# LPF.net
KiCad netlist of a schematic drawn in Altium Designer
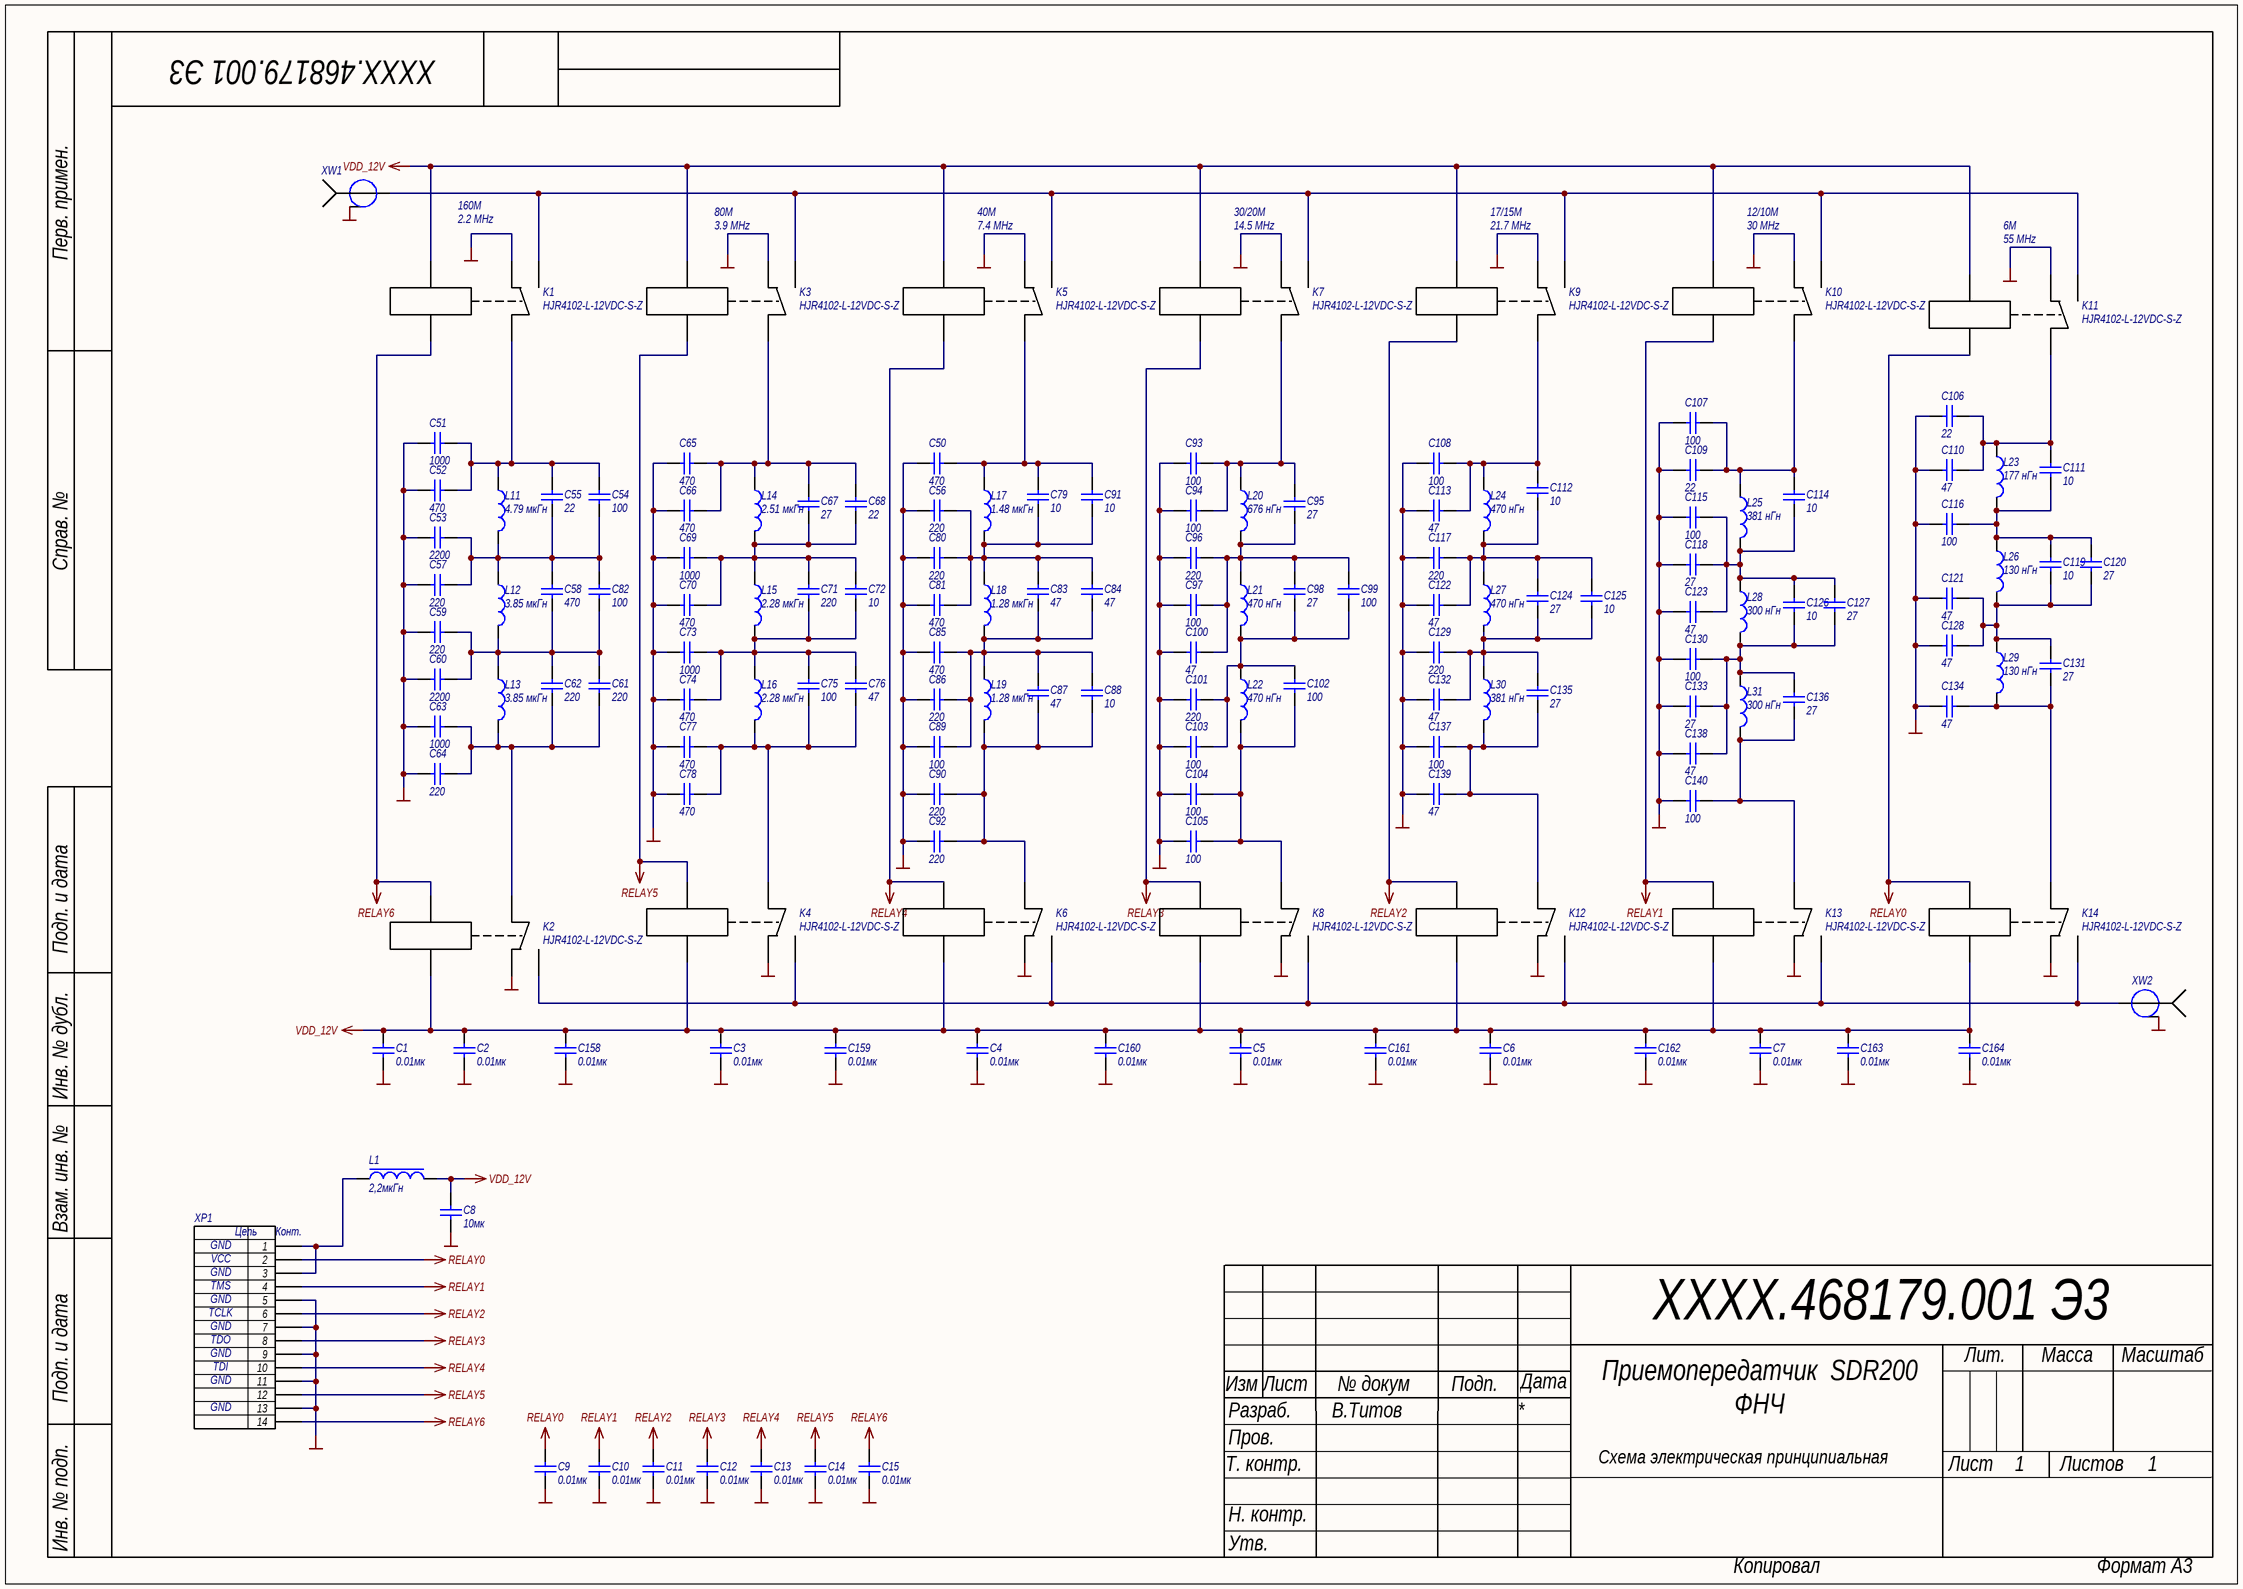
[diagram p0: LPF.SchDoc]

(export (version "E")
  (design (tool "Eeschema 10.0.6"))
  (components
    (comp (ref "C1")
      (value "0.01мк")
      (footprint "CAPC1005X06N")
      (description "Кер. ЧИП-конденсатор")
      (fields (field (name "TOLERANCE") "±20%"))
      (libsource (lib "nels_caps") (part "Кер.ЧИП конд. 0402 0.01мкФ X7R 10%, 50В"))
    )
    (comp (ref "C2")
      (value "0.01мк")
      (footprint "CAPC1005X06N")
      (description "Кер. ЧИП-конденсатор")
      (fields (field (name "TOLERANCE") "±20%"))
      (libsource (lib "nels_caps") (part "Кер.ЧИП конд. 0402 0.01мкФ X7R 10%, 50В"))
    )
    (comp (ref "C3")
      (value "0.01мк")
      (footprint "CAPC1005X06N")
      (description "Кер. ЧИП-конденсатор")
      (fields (field (name "TOLERANCE") "±20%"))
      (libsource (lib "nels_caps") (part "Кер.ЧИП конд. 0402 0.01мкФ X7R 10%, 50В"))
    )
    (comp (ref "C4")
      (value "0.01мк")
      (footprint "CAPC1005X06N")
      (description "Кер. ЧИП-конденсатор")
      (fields (field (name "TOLERANCE") "±20%"))
      (libsource (lib "nels_caps") (part "Кер.ЧИП конд. 0402 0.01мкФ X7R 10%, 50В"))
    )
    (comp (ref "C5")
      (value "0.01мк")
      (footprint "CAPC1005X06N")
      (description "Кер. ЧИП-конденсатор")
      (fields (field (name "TOLERANCE") "±20%"))
      (libsource (lib "nels_caps") (part "Кер.ЧИП конд. 0402 0.01мкФ X7R 10%, 50В"))
    )
    (comp (ref "C6")
      (value "0.01мк")
      (footprint "CAPC1005X06N")
      (description "Кер. ЧИП-конденсатор")
      (fields (field (name "TOLERANCE") "±20%"))
      (libsource (lib "nels_caps") (part "Кер.ЧИП конд. 0402 0.01мкФ X7R 10%, 50В"))
    )
    (comp (ref "C7")
      (value "0.01мк")
      (footprint "CAPC1005X06N")
      (description "Кер. ЧИП-конденсатор")
      (fields (field (name "TOLERANCE") "±20%"))
      (libsource (lib "nels_caps") (part "Кер.ЧИП конд. 0402 0.01мкФ X7R 10%, 50В"))
    )
    (comp (ref "C8")
      (value "10мк")
      (footprint "CAPC3225X27L")
      (description "Кер. ЧИП-конденсатор")
      (fields (field (name "MANUFACTURER") "Murata") (field (name "TOLERANCE") "±20%"))
      (libsource (lib "nels_caps") (part "Кер.ЧИП конд. 1210 10мкФ X5R 20% 50В"))
    )
    (comp (ref "C9")
      (value "0.01мк")
      (footprint "CAPC1005X06N")
      (description "Кер. ЧИП-конденсатор")
      (fields (field (name "TOLERANCE") "±20%"))
      (libsource (lib "nels_caps") (part "Кер.ЧИП конд. 0402 0.01мкФ X7R 10%, 50В"))
    )
    (comp (ref "C10")
      (value "0.01мк")
      (footprint "CAPC1005X06N")
      (description "Кер. ЧИП-конденсатор")
      (fields (field (name "TOLERANCE") "±20%"))
      (libsource (lib "nels_caps") (part "Кер.ЧИП конд. 0402 0.01мкФ X7R 10%, 50В"))
    )
    (comp (ref "C11")
      (value "0.01мк")
      (footprint "CAPC1005X06N")
      (description "Кер. ЧИП-конденсатор")
      (fields (field (name "TOLERANCE") "±20%"))
      (libsource (lib "nels_caps") (part "Кер.ЧИП конд. 0402 0.01мкФ X7R 10%, 50В"))
    )
    (comp (ref "C12")
      (value "0.01мк")
      (footprint "CAPC1005X06N")
      (description "Кер. ЧИП-конденсатор")
      (fields (field (name "TOLERANCE") "±20%"))
      (libsource (lib "nels_caps") (part "Кер.ЧИП конд. 0402 0.01мкФ X7R 10%, 50В"))
    )
    (comp (ref "C13")
      (value "0.01мк")
      (footprint "CAPC1005X06N")
      (description "Кер. ЧИП-конденсатор")
      (fields (field (name "TOLERANCE") "±20%"))
      (libsource (lib "nels_caps") (part "Кер.ЧИП конд. 0402 0.01мкФ X7R 10%, 50В"))
    )
    (comp (ref "C14")
      (value "0.01мк")
      (footprint "CAPC1005X06N")
      (description "Кер. ЧИП-конденсатор")
      (fields (field (name "TOLERANCE") "±20%"))
      (libsource (lib "nels_caps") (part "Кер.ЧИП конд. 0402 0.01мкФ X7R 10%, 50В"))
    )
    (comp (ref "C15")
      (value "0.01мк")
      (footprint "CAPC1005X06N")
      (description "Кер. ЧИП-конденсатор")
      (fields (field (name "TOLERANCE") "±20%"))
      (libsource (lib "nels_caps") (part "Кер.ЧИП конд. 0402 0.01мкФ X7R 10%, 50В"))
    )
    (comp (ref "C50")
      (value "470")
      (footprint "CAPC3216X19L")
      (description "Кер. ЧИП-конденсатор")
      (fields (field (name "MANUFACTURER") "WALSIN") (field (name "TOLERANCE") "±10%"))
      (libsource (lib "nels_caps") (part "Кер.ЧИП конд. 1206 470пФ NP0 10% 2000В"))
    )
    (comp (ref "C51")
      (value "1000")
      (footprint "CAPC3216X19L")
      (description "Кер. ЧИП-конденсатор")
      (fields (field (name "MANUFACTURER") "Johanson") (field (name "TOLERANCE") "±10%"))
      (libsource (lib "nels_caps") (part "Кер.ЧИП конд. 1206 1000пФ X7К 10% 2000В"))
    )
    (comp (ref "C52")
      (value "470")
      (footprint "CAPC3216X19L")
      (description "Кер. ЧИП-конденсатор")
      (fields (field (name "MANUFACTURER") "WALSIN") (field (name "TOLERANCE") "±10%"))
      (libsource (lib "nels_caps") (part "Кер.ЧИП конд. 1206 470пФ NP0 10% 2000В"))
    )
    (comp (ref "C53")
      (value "2200")
      (footprint "CAPC3216X19L")
      (description "Кер. ЧИП-конденсатор")
      (fields (field (name "MANUFACTURER") "WALSIN") (field (name "TOLERANCE") "±10%"))
      (libsource (lib "nels_caps") (part "Кер.ЧИП конд. 1206 2200пФ X7К 10% 1000В"))
    )
    (comp (ref "C54")
      (value "100")
      (footprint "CAPC3216X19L")
      (description "Кер. ЧИП-конденсатор")
      (fields (field (name "MANUFACTURER") "WALSIN") (field (name "TOLERANCE") "±5%"))
      (libsource (lib "nels_caps") (part "Кер.ЧИП конд. 1206 100пФ NP0 5% 2000В"))
    )
    (comp (ref "C55")
      (value "22")
      (footprint "CAPC3216X19L")
      (description "Кер. ЧИП-конденсатор")
      (fields (field (name "MANUFACTURER") "WALSIN") (field (name "TOLERANCE") "±5%"))
      (libsource (lib "nels_caps") (part "Кер.ЧИП конд. 1206 22пФ NP0 5% 2000В"))
    )
    (comp (ref "C56")
      (value "220")
      (footprint "CAPC3216X19L")
      (description "Кер. ЧИП-конденсатор")
      (fields (field (name "MANUFACTURER") "Johanson") (field (name "TOLERANCE") "±10%"))
      (libsource (lib "nels_caps") (part "Кер.ЧИП конд. 1206 220пФ NP0 5% 2000В"))
    )
    (comp (ref "C57")
      (value "220")
      (footprint "CAPC3216X19L")
      (description "Кер. ЧИП-конденсатор")
      (fields (field (name "MANUFACTURER") "Johanson") (field (name "TOLERANCE") "±10%"))
      (libsource (lib "nels_caps") (part "Кер.ЧИП конд. 1206 220пФ NP0 5% 2000В"))
    )
    (comp (ref "C58")
      (value "470")
      (footprint "CAPC3216X19L")
      (description "Кер. ЧИП-конденсатор")
      (fields (field (name "MANUFACTURER") "WALSIN") (field (name "TOLERANCE") "±10%"))
      (libsource (lib "nels_caps") (part "Кер.ЧИП конд. 1206 470пФ NP0 10% 2000В"))
    )
    (comp (ref "C59")
      (value "220")
      (footprint "CAPC3216X19L")
      (description "Кер. ЧИП-конденсатор")
      (fields (field (name "MANUFACTURER") "Johanson") (field (name "TOLERANCE") "±10%"))
      (libsource (lib "nels_caps") (part "Кер.ЧИП конд. 1206 220пФ NP0 5% 2000В"))
    )
    (comp (ref "C60")
      (value "2200")
      (footprint "CAPC3216X19L")
      (description "Кер. ЧИП-конденсатор")
      (fields (field (name "MANUFACTURER") "WALSIN") (field (name "TOLERANCE") "±10%"))
      (libsource (lib "nels_caps") (part "Кер.ЧИП конд. 1206 2200пФ X7К 10% 1000В"))
    )
    (comp (ref "C61")
      (value "220")
      (footprint "CAPC3216X19L")
      (description "Кер. ЧИП-конденсатор")
      (fields (field (name "MANUFACTURER") "Johanson") (field (name "TOLERANCE") "±10%"))
      (libsource (lib "nels_caps") (part "Кер.ЧИП конд. 1206 220пФ NP0 5% 2000В"))
    )
    (comp (ref "C62")
      (value "220")
      (footprint "CAPC3216X19L")
      (description "Кер. ЧИП-конденсатор")
      (fields (field (name "MANUFACTURER") "Johanson") (field (name "TOLERANCE") "±10%"))
      (libsource (lib "nels_caps") (part "Кер.ЧИП конд. 1206 220пФ NP0 5% 2000В"))
    )
    (comp (ref "C63")
      (value "1000")
      (footprint "CAPC3216X19L")
      (description "Кер. ЧИП-конденсатор")
      (fields (field (name "MANUFACTURER") "Johanson") (field (name "TOLERANCE") "±10%"))
      (libsource (lib "nels_caps") (part "Кер.ЧИП конд. 1206 1000пФ X7К 10% 2000В"))
    )
    (comp (ref "C64")
      (value "220")
      (footprint "CAPC3216X19L")
      (description "Кер. ЧИП-конденсатор")
      (fields (field (name "MANUFACTURER") "Johanson") (field (name "TOLERANCE") "±10%"))
      (libsource (lib "nels_caps") (part "Кер.ЧИП конд. 1206 220пФ NP0 5% 2000В"))
    )
    (comp (ref "C65")
      (value "470")
      (footprint "CAPC3216X19L")
      (description "Кер. ЧИП-конденсатор")
      (fields (field (name "MANUFACTURER") "WALSIN") (field (name "TOLERANCE") "±10%"))
      (libsource (lib "nels_caps") (part "Кер.ЧИП конд. 1206 470пФ NP0 10% 2000В"))
    )
    (comp (ref "C66")
      (value "470")
      (footprint "CAPC3216X19L")
      (description "Кер. ЧИП-конденсатор")
      (fields (field (name "MANUFACTURER") "WALSIN") (field (name "TOLERANCE") "±10%"))
      (libsource (lib "nels_caps") (part "Кер.ЧИП конд. 1206 470пФ NP0 10% 2000В"))
    )
    (comp (ref "C67")
      (value "27")
      (footprint "CAPC3216X19L")
      (description "Кер. ЧИП-конденсатор")
      (fields (field (name "MANUFACTURER") "WALSIN") (field (name "TOLERANCE") "±10%"))
      (libsource (lib "nels_caps") (part "Кер.ЧИП конд. 1206 27пФ NP0 10% 2000В"))
    )
    (comp (ref "C68")
      (value "22")
      (footprint "CAPC3216X19L")
      (description "Кер. ЧИП-конденсатор")
      (fields (field (name "MANUFACTURER") "WALSIN") (field (name "TOLERANCE") "±5%"))
      (libsource (lib "nels_caps") (part "Кер.ЧИП конд. 1206 22пФ NP0 5% 2000В"))
    )
    (comp (ref "C69")
      (value "1000")
      (footprint "CAPC3216X19L")
      (description "Кер. ЧИП-конденсатор")
      (fields (field (name "MANUFACTURER") "Johanson") (field (name "TOLERANCE") "±10%"))
      (libsource (lib "nels_caps") (part "Кер.ЧИП конд. 1206 1000пФ X7К 10% 2000В"))
    )
    (comp (ref "C70")
      (value "470")
      (footprint "CAPC3216X19L")
      (description "Кер. ЧИП-конденсатор")
      (fields (field (name "MANUFACTURER") "WALSIN") (field (name "TOLERANCE") "±10%"))
      (libsource (lib "nels_caps") (part "Кер.ЧИП конд. 1206 470пФ NP0 10% 2000В"))
    )
    (comp (ref "C71")
      (value "220")
      (footprint "CAPC3216X19L")
      (description "Кер. ЧИП-конденсатор")
      (fields (field (name "MANUFACTURER") "Johanson") (field (name "TOLERANCE") "±10%"))
      (libsource (lib "nels_caps") (part "Кер.ЧИП конд. 1206 220пФ NP0 5% 2000В"))
    )
    (comp (ref "C72")
      (value "10")
      (footprint "CAPC3216X19L")
      (description "Кер. ЧИП-конденсатор")
      (fields (field (name "MANUFACTURER") "WALSIN") (field (name "TOLERANCE") "±5%"))
      (libsource (lib "nels_caps") (part "Кер.ЧИП конд. 1206 10пФ NP0 5% 2000В"))
    )
    (comp (ref "C73")
      (value "1000")
      (footprint "CAPC3216X19L")
      (description "Кер. ЧИП-конденсатор")
      (fields (field (name "MANUFACTURER") "Johanson") (field (name "TOLERANCE") "±10%"))
      (libsource (lib "nels_caps") (part "Кер.ЧИП конд. 1206 1000пФ X7К 10% 2000В"))
    )
    (comp (ref "C74")
      (value "470")
      (footprint "CAPC3216X19L")
      (description "Кер. ЧИП-конденсатор")
      (fields (field (name "MANUFACTURER") "WALSIN") (field (name "TOLERANCE") "±10%"))
      (libsource (lib "nels_caps") (part "Кер.ЧИП конд. 1206 470пФ NP0 10% 2000В"))
    )
    (comp (ref "C75")
      (value "100")
      (footprint "CAPC3216X19L")
      (description "Кер. ЧИП-конденсатор")
      (fields (field (name "MANUFACTURER") "WALSIN") (field (name "TOLERANCE") "±5%"))
      (libsource (lib "nels_caps") (part "Кер.ЧИП конд. 1206 100пФ NP0 5% 2000В"))
    )
    (comp (ref "C76")
      (value "47")
      (footprint "CAPC3216X19L")
      (description "Кер. ЧИП-конденсатор")
      (fields (field (name "MANUFACTURER") "WALSIN") (field (name "TOLERANCE") "±5%"))
      (libsource (lib "nels_caps") (part "Кер.ЧИП конд. 1206 47пФ NP0 5% 2000В"))
    )
    (comp (ref "C77")
      (value "470")
      (footprint "CAPC3216X19L")
      (description "Кер. ЧИП-конденсатор")
      (fields (field (name "MANUFACTURER") "WALSIN") (field (name "TOLERANCE") "±10%"))
      (libsource (lib "nels_caps") (part "Кер.ЧИП конд. 1206 470пФ NP0 10% 2000В"))
    )
    (comp (ref "C78")
      (value "470")
      (footprint "CAPC3216X19L")
      (description "Кер. ЧИП-конденсатор")
      (fields (field (name "MANUFACTURER") "WALSIN") (field (name "TOLERANCE") "±10%"))
      (libsource (lib "nels_caps") (part "Кер.ЧИП конд. 1206 470пФ NP0 10% 2000В"))
    )
    (comp (ref "C79")
      (value "10")
      (footprint "CAPC3216X19L")
      (description "Кер. ЧИП-конденсатор")
      (fields (field (name "MANUFACTURER") "WALSIN") (field (name "TOLERANCE") "±5%"))
      (libsource (lib "nels_caps") (part "Кер.ЧИП конд. 1206 10пФ NP0 5% 2000В"))
    )
    (comp (ref "C80")
      (value "220")
      (footprint "CAPC3216X19L")
      (description "Кер. ЧИП-конденсатор")
      (fields (field (name "MANUFACTURER") "Johanson") (field (name "TOLERANCE") "±10%"))
      (libsource (lib "nels_caps") (part "Кер.ЧИП конд. 1206 220пФ NP0 5% 2000В"))
    )
    (comp (ref "C81")
      (value "470")
      (footprint "CAPC3216X19L")
      (description "Кер. ЧИП-конденсатор")
      (fields (field (name "MANUFACTURER") "WALSIN") (field (name "TOLERANCE") "±10%"))
      (libsource (lib "nels_caps") (part "Кер.ЧИП конд. 1206 470пФ NP0 10% 2000В"))
    )
    (comp (ref "C82")
      (value "100")
      (footprint "CAPC3216X19L")
      (description "Кер. ЧИП-конденсатор")
      (fields (field (name "MANUFACTURER") "WALSIN") (field (name "TOLERANCE") "±5%"))
      (libsource (lib "nels_caps") (part "Кер.ЧИП конд. 1206 100пФ NP0 5% 2000В"))
    )
    (comp (ref "C83")
      (value "47")
      (footprint "CAPC3216X19L")
      (description "Кер. ЧИП-конденсатор")
      (fields (field (name "MANUFACTURER") "WALSIN") (field (name "TOLERANCE") "±5%"))
      (libsource (lib "nels_caps") (part "Кер.ЧИП конд. 1206 47пФ NP0 5% 2000В"))
    )
    (comp (ref "C84")
      (value "47")
      (footprint "CAPC3216X19L")
      (description "Кер. ЧИП-конденсатор")
      (fields (field (name "MANUFACTURER") "WALSIN") (field (name "TOLERANCE") "±5%"))
      (libsource (lib "nels_caps") (part "Кер.ЧИП конд. 1206 47пФ NP0 5% 2000В"))
    )
    (comp (ref "C85")
      (value "470")
      (footprint "CAPC3216X19L")
      (description "Кер. ЧИП-конденсатор")
      (fields (field (name "MANUFACTURER") "WALSIN") (field (name "TOLERANCE") "±10%"))
      (libsource (lib "nels_caps") (part "Кер.ЧИП конд. 1206 470пФ NP0 10% 2000В"))
    )
    (comp (ref "C86")
      (value "220")
      (footprint "CAPC3216X19L")
      (description "Кер. ЧИП-конденсатор")
      (fields (field (name "MANUFACTURER") "Johanson") (field (name "TOLERANCE") "±10%"))
      (libsource (lib "nels_caps") (part "Кер.ЧИП конд. 1206 220пФ NP0 5% 2000В"))
    )
    (comp (ref "C87")
      (value "47")
      (footprint "CAPC3216X19L")
      (description "Кер. ЧИП-конденсатор")
      (fields (field (name "MANUFACTURER") "WALSIN") (field (name "TOLERANCE") "±5%"))
      (libsource (lib "nels_caps") (part "Кер.ЧИП конд. 1206 47пФ NP0 5% 2000В"))
    )
    (comp (ref "C88")
      (value "10")
      (footprint "CAPC3216X19L")
      (description "Кер. ЧИП-конденсатор")
      (fields (field (name "MANUFACTURER") "WALSIN") (field (name "TOLERANCE") "±5%"))
      (libsource (lib "nels_caps") (part "Кер.ЧИП конд. 1206 10пФ NP0 5% 2000В"))
    )
    (comp (ref "C89")
      (value "100")
      (footprint "CAPC3216X19L")
      (description "Кер. ЧИП-конденсатор")
      (fields (field (name "MANUFACTURER") "WALSIN") (field (name "TOLERANCE") "±5%"))
      (libsource (lib "nels_caps") (part "Кер.ЧИП конд. 1206 100пФ NP0 5% 2000В"))
    )
    (comp (ref "C90")
      (value "220")
      (footprint "CAPC3216X19L")
      (description "Кер. ЧИП-конденсатор")
      (fields (field (name "MANUFACTURER") "Johanson") (field (name "TOLERANCE") "±10%"))
      (libsource (lib "nels_caps") (part "Кер.ЧИП конд. 1206 220пФ NP0 5% 2000В"))
    )
    (comp (ref "C91")
      (value "10")
      (footprint "CAPC3216X19L")
      (description "Кер. ЧИП-конденсатор")
      (fields (field (name "MANUFACTURER") "WALSIN") (field (name "TOLERANCE") "±5%"))
      (libsource (lib "nels_caps") (part "Кер.ЧИП конд. 1206 10пФ NP0 5% 2000В"))
    )
    (comp (ref "C92")
      (value "220")
      (footprint "CAPC3216X19L")
      (description "Кер. ЧИП-конденсатор")
      (fields (field (name "MANUFACTURER") "Johanson") (field (name "TOLERANCE") "±10%"))
      (libsource (lib "nels_caps") (part "Кер.ЧИП конд. 1206 220пФ NP0 5% 2000В"))
    )
    (comp (ref "C93")
      (value "100")
      (footprint "CAPC3216X19L")
      (description "Кер. ЧИП-конденсатор")
      (fields (field (name "MANUFACTURER") "WALSIN") (field (name "TOLERANCE") "±5%"))
      (libsource (lib "nels_caps") (part "Кер.ЧИП конд. 1206 100пФ NP0 5% 2000В"))
    )
    (comp (ref "C94")
      (value "100")
      (footprint "CAPC3216X19L")
      (description "Кер. ЧИП-конденсатор")
      (fields (field (name "MANUFACTURER") "WALSIN") (field (name "TOLERANCE") "±5%"))
      (libsource (lib "nels_caps") (part "Кер.ЧИП конд. 1206 100пФ NP0 5% 2000В"))
    )
    (comp (ref "C95")
      (value "27")
      (footprint "CAPC3216X19L")
      (description "Кер. ЧИП-конденсатор")
      (fields (field (name "MANUFACTURER") "WALSIN") (field (name "TOLERANCE") "±10%"))
      (libsource (lib "nels_caps") (part "Кер.ЧИП конд. 1206 27пФ NP0 10% 2000В"))
    )
    (comp (ref "C96")
      (value "220")
      (footprint "CAPC3216X19L")
      (description "Кер. ЧИП-конденсатор")
      (fields (field (name "MANUFACTURER") "Johanson") (field (name "TOLERANCE") "±10%"))
      (libsource (lib "nels_caps") (part "Кер.ЧИП конд. 1206 220пФ NP0 5% 2000В"))
    )
    (comp (ref "C97")
      (value "100")
      (footprint "CAPC3216X19L")
      (description "Кер. ЧИП-конденсатор")
      (fields (field (name "MANUFACTURER") "WALSIN") (field (name "TOLERANCE") "±5%"))
      (libsource (lib "nels_caps") (part "Кер.ЧИП конд. 1206 100пФ NP0 5% 2000В"))
    )
    (comp (ref "C98")
      (value "27")
      (footprint "CAPC3216X19L")
      (description "Кер. ЧИП-конденсатор")
      (fields (field (name "MANUFACTURER") "WALSIN") (field (name "TOLERANCE") "±10%"))
      (libsource (lib "nels_caps") (part "Кер.ЧИП конд. 1206 27пФ NP0 10% 2000В"))
    )
    (comp (ref "C99")
      (value "100")
      (footprint "CAPC3216X19L")
      (description "Кер. ЧИП-конденсатор")
      (fields (field (name "MANUFACTURER") "WALSIN") (field (name "TOLERANCE") "±5%"))
      (libsource (lib "nels_caps") (part "Кер.ЧИП конд. 1206 100пФ NP0 5% 2000В"))
    )
    (comp (ref "C100")
      (value "47")
      (footprint "CAPC3216X19L")
      (description "Кер. ЧИП-конденсатор")
      (fields (field (name "MANUFACTURER") "WALSIN") (field (name "TOLERANCE") "±5%"))
      (libsource (lib "nels_caps") (part "Кер.ЧИП конд. 1206 47пФ NP0 5% 2000В"))
    )
    (comp (ref "C101")
      (value "220")
      (footprint "CAPC3216X19L")
      (description "Кер. ЧИП-конденсатор")
      (fields (field (name "MANUFACTURER") "Johanson") (field (name "TOLERANCE") "±10%"))
      (libsource (lib "nels_caps") (part "Кер.ЧИП конд. 1206 220пФ NP0 5% 2000В"))
    )
    (comp (ref "C102")
      (value "100")
      (footprint "CAPC3216X19L")
      (description "Кер. ЧИП-конденсатор")
      (fields (field (name "MANUFACTURER") "WALSIN") (field (name "TOLERANCE") "±5%"))
      (libsource (lib "nels_caps") (part "Кер.ЧИП конд. 1206 100пФ NP0 5% 2000В"))
    )
    (comp (ref "C103")
      (value "100")
      (footprint "CAPC3216X19L")
      (description "Кер. ЧИП-конденсатор")
      (fields (field (name "MANUFACTURER") "WALSIN") (field (name "TOLERANCE") "±5%"))
      (libsource (lib "nels_caps") (part "Кер.ЧИП конд. 1206 100пФ NP0 5% 2000В"))
    )
    (comp (ref "C104")
      (value "100")
      (footprint "CAPC3216X19L")
      (description "Кер. ЧИП-конденсатор")
      (fields (field (name "MANUFACTURER") "WALSIN") (field (name "TOLERANCE") "±5%"))
      (libsource (lib "nels_caps") (part "Кер.ЧИП конд. 1206 100пФ NP0 5% 2000В"))
    )
    (comp (ref "C105")
      (value "100")
      (footprint "CAPC3216X19L")
      (description "Кер. ЧИП-конденсатор")
      (fields (field (name "MANUFACTURER") "WALSIN") (field (name "TOLERANCE") "±5%"))
      (libsource (lib "nels_caps") (part "Кер.ЧИП конд. 1206 100пФ NP0 5% 2000В"))
    )
    (comp (ref "C106")
      (value "22")
      (footprint "CAPC3216X19L")
      (description "Кер. ЧИП-конденсатор")
      (fields (field (name "MANUFACTURER") "WALSIN") (field (name "TOLERANCE") "±5%"))
      (libsource (lib "nels_caps") (part "Кер.ЧИП конд. 1206 22пФ NP0 5% 2000В"))
    )
    (comp (ref "C107")
      (value "100")
      (footprint "CAPC3216X19L")
      (description "Кер. ЧИП-конденсатор")
      (fields (field (name "MANUFACTURER") "WALSIN") (field (name "TOLERANCE") "±5%"))
      (libsource (lib "nels_caps") (part "Кер.ЧИП конд. 1206 100пФ NP0 5% 2000В"))
    )
    (comp (ref "C108")
      (value "100")
      (footprint "CAPC3216X19L")
      (description "Кер. ЧИП-конденсатор")
      (fields (field (name "MANUFACTURER") "WALSIN") (field (name "TOLERANCE") "±5%"))
      (libsource (lib "nels_caps") (part "Кер.ЧИП конд. 1206 100пФ NP0 5% 2000В"))
    )
    (comp (ref "C109")
      (value "22")
      (footprint "CAPC3216X19L")
      (description "Кер. ЧИП-конденсатор")
      (fields (field (name "MANUFACTURER") "WALSIN") (field (name "TOLERANCE") "±5%"))
      (libsource (lib "nels_caps") (part "Кер.ЧИП конд. 1206 22пФ NP0 5% 2000В"))
    )
    (comp (ref "C110")
      (value "47")
      (footprint "CAPC3216X19L")
      (description "Кер. ЧИП-конденсатор")
      (fields (field (name "MANUFACTURER") "WALSIN") (field (name "TOLERANCE") "±5%"))
      (libsource (lib "nels_caps") (part "Кер.ЧИП конд. 1206 47пФ NP0 5% 2000В"))
    )
    (comp (ref "C111")
      (value "10")
      (footprint "CAPC3216X19L")
      (description "Кер. ЧИП-конденсатор")
      (fields (field (name "MANUFACTURER") "WALSIN") (field (name "TOLERANCE") "±5%"))
      (libsource (lib "nels_caps") (part "Кер.ЧИП конд. 1206 10пФ NP0 5% 2000В"))
    )
    (comp (ref "C112")
      (value "10")
      (footprint "CAPC3216X19L")
      (description "Кер. ЧИП-конденсатор")
      (fields (field (name "MANUFACTURER") "WALSIN") (field (name "TOLERANCE") "±5%"))
      (libsource (lib "nels_caps") (part "Кер.ЧИП конд. 1206 10пФ NP0 5% 2000В"))
    )
    (comp (ref "C113")
      (value "47")
      (footprint "CAPC3216X19L")
      (description "Кер. ЧИП-конденсатор")
      (fields (field (name "MANUFACTURER") "WALSIN") (field (name "TOLERANCE") "±5%"))
      (libsource (lib "nels_caps") (part "Кер.ЧИП конд. 1206 47пФ NP0 5% 2000В"))
    )
    (comp (ref "C114")
      (value "10")
      (footprint "CAPC3216X19L")
      (description "Кер. ЧИП-конденсатор")
      (fields (field (name "MANUFACTURER") "WALSIN") (field (name "TOLERANCE") "±5%"))
      (libsource (lib "nels_caps") (part "Кер.ЧИП конд. 1206 10пФ NP0 5% 2000В"))
    )
    (comp (ref "C115")
      (value "100")
      (footprint "CAPC3216X19L")
      (description "Кер. ЧИП-конденсатор")
      (fields (field (name "MANUFACTURER") "WALSIN") (field (name "TOLERANCE") "±5%"))
      (libsource (lib "nels_caps") (part "Кер.ЧИП конд. 1206 100пФ NP0 5% 2000В"))
    )
    (comp (ref "C116")
      (value "100")
      (footprint "CAPC3216X19L")
      (description "Кер. ЧИП-конденсатор")
      (fields (field (name "MANUFACTURER") "WALSIN") (field (name "TOLERANCE") "±5%"))
      (libsource (lib "nels_caps") (part "Кер.ЧИП конд. 1206 100пФ NP0 5% 2000В"))
    )
    (comp (ref "C117")
      (value "220")
      (footprint "CAPC3216X19L")
      (description "Кер. ЧИП-конденсатор")
      (fields (field (name "MANUFACTURER") "Johanson") (field (name "TOLERANCE") "±10%"))
      (libsource (lib "nels_caps") (part "Кер.ЧИП конд. 1206 220пФ NP0 5% 2000В"))
    )
    (comp (ref "C118")
      (value "27")
      (footprint "CAPC3216X19L")
      (description "Кер. ЧИП-конденсатор")
      (fields (field (name "MANUFACTURER") "WALSIN") (field (name "TOLERANCE") "±10%"))
      (libsource (lib "nels_caps") (part "Кер.ЧИП конд. 1206 27пФ NP0 10% 2000В"))
    )
    (comp (ref "C119")
      (value "10")
      (footprint "CAPC3216X19L")
      (description "Кер. ЧИП-конденсатор")
      (fields (field (name "MANUFACTURER") "WALSIN") (field (name "TOLERANCE") "±5%"))
      (libsource (lib "nels_caps") (part "Кер.ЧИП конд. 1206 10пФ NP0 5% 2000В"))
    )
    (comp (ref "C120")
      (value "27")
      (footprint "CAPC3216X19L")
      (description "Кер. ЧИП-конденсатор")
      (fields (field (name "MANUFACTURER") "WALSIN") (field (name "TOLERANCE") "±10%"))
      (libsource (lib "nels_caps") (part "Кер.ЧИП конд. 1206 27пФ NP0 10% 2000В"))
    )
    (comp (ref "C121")
      (value "47")
      (footprint "CAPC3216X19L")
      (description "Кер. ЧИП-конденсатор")
      (fields (field (name "MANUFACTURER") "WALSIN") (field (name "TOLERANCE") "±5%"))
      (libsource (lib "nels_caps") (part "Кер.ЧИП конд. 1206 47пФ NP0 5% 2000В"))
    )
    (comp (ref "C122")
      (value "47")
      (footprint "CAPC3216X19L")
      (description "Кер. ЧИП-конденсатор")
      (fields (field (name "MANUFACTURER") "WALSIN") (field (name "TOLERANCE") "±5%"))
      (libsource (lib "nels_caps") (part "Кер.ЧИП конд. 1206 47пФ NP0 5% 2000В"))
    )
    (comp (ref "C123")
      (value "47")
      (footprint "CAPC3216X19L")
      (description "Кер. ЧИП-конденсатор")
      (fields (field (name "MANUFACTURER") "WALSIN") (field (name "TOLERANCE") "±5%"))
      (libsource (lib "nels_caps") (part "Кер.ЧИП конд. 1206 47пФ NP0 5% 2000В"))
    )
    (comp (ref "C124")
      (value "27")
      (footprint "CAPC3216X19L")
      (description "Кер. ЧИП-конденсатор")
      (fields (field (name "MANUFACTURER") "WALSIN") (field (name "TOLERANCE") "±10%"))
      (libsource (lib "nels_caps") (part "Кер.ЧИП конд. 1206 27пФ NP0 10% 2000В"))
    )
    (comp (ref "C125")
      (value "10")
      (footprint "CAPC3216X19L")
      (description "Кер. ЧИП-конденсатор")
      (fields (field (name "MANUFACTURER") "WALSIN") (field (name "TOLERANCE") "±5%"))
      (libsource (lib "nels_caps") (part "Кер.ЧИП конд. 1206 10пФ NP0 5% 2000В"))
    )
    (comp (ref "C126")
      (value "10")
      (footprint "CAPC3216X19L")
      (description "Кер. ЧИП-конденсатор")
      (fields (field (name "MANUFACTURER") "WALSIN") (field (name "TOLERANCE") "±5%"))
      (libsource (lib "nels_caps") (part "Кер.ЧИП конд. 1206 10пФ NP0 5% 2000В"))
    )
    (comp (ref "C127")
      (value "27")
      (footprint "CAPC3216X19L")
      (description "Кер. ЧИП-конденсатор")
      (fields (field (name "MANUFACTURER") "WALSIN") (field (name "TOLERANCE") "±10%"))
      (libsource (lib "nels_caps") (part "Кер.ЧИП конд. 1206 27пФ NP0 10% 2000В"))
    )
    (comp (ref "C128")
      (value "47")
      (footprint "CAPC3216X19L")
      (description "Кер. ЧИП-конденсатор")
      (fields (field (name "MANUFACTURER") "WALSIN") (field (name "TOLERANCE") "±5%"))
      (libsource (lib "nels_caps") (part "Кер.ЧИП конд. 1206 47пФ NP0 5% 2000В"))
    )
    (comp (ref "C129")
      (value "220")
      (footprint "CAPC3216X19L")
      (description "Кер. ЧИП-конденсатор")
      (fields (field (name "MANUFACTURER") "Johanson") (field (name "TOLERANCE") "±10%"))
      (libsource (lib "nels_caps") (part "Кер.ЧИП конд. 1206 220пФ NP0 5% 2000В"))
    )
    (comp (ref "C130")
      (value "100")
      (footprint "CAPC3216X19L")
      (description "Кер. ЧИП-конденсатор")
      (fields (field (name "MANUFACTURER") "WALSIN") (field (name "TOLERANCE") "±5%"))
      (libsource (lib "nels_caps") (part "Кер.ЧИП конд. 1206 100пФ NP0 5% 2000В"))
    )
    (comp (ref "C131")
      (value "27")
      (footprint "CAPC3216X19L")
      (description "Кер. ЧИП-конденсатор")
      (fields (field (name "MANUFACTURER") "WALSIN") (field (name "TOLERANCE") "±10%"))
      (libsource (lib "nels_caps") (part "Кер.ЧИП конд. 1206 27пФ NP0 10% 2000В"))
    )
    (comp (ref "C132")
      (value "47")
      (footprint "CAPC3216X19L")
      (description "Кер. ЧИП-конденсатор")
      (fields (field (name "MANUFACTURER") "WALSIN") (field (name "TOLERANCE") "±5%"))
      (libsource (lib "nels_caps") (part "Кер.ЧИП конд. 1206 47пФ NP0 5% 2000В"))
    )
    (comp (ref "C133")
      (value "27")
      (footprint "CAPC3216X19L")
      (description "Кер. ЧИП-конденсатор")
      (fields (field (name "MANUFACTURER") "WALSIN") (field (name "TOLERANCE") "±10%"))
      (libsource (lib "nels_caps") (part "Кер.ЧИП конд. 1206 27пФ NP0 10% 2000В"))
    )
    (comp (ref "C134")
      (value "47")
      (footprint "CAPC3216X19L")
      (description "Кер. ЧИП-конденсатор")
      (fields (field (name "MANUFACTURER") "WALSIN") (field (name "TOLERANCE") "±5%"))
      (libsource (lib "nels_caps") (part "Кер.ЧИП конд. 1206 47пФ NP0 5% 2000В"))
    )
    (comp (ref "C135")
      (value "27")
      (footprint "CAPC3216X19L")
      (description "Кер. ЧИП-конденсатор")
      (fields (field (name "MANUFACTURER") "WALSIN") (field (name "TOLERANCE") "±10%"))
      (libsource (lib "nels_caps") (part "Кер.ЧИП конд. 1206 27пФ NP0 10% 2000В"))
    )
    (comp (ref "C136")
      (value "27")
      (footprint "CAPC3216X19L")
      (description "Кер. ЧИП-конденсатор")
      (fields (field (name "MANUFACTURER") "WALSIN") (field (name "TOLERANCE") "±10%"))
      (libsource (lib "nels_caps") (part "Кер.ЧИП конд. 1206 27пФ NP0 10% 2000В"))
    )
    (comp (ref "C137")
      (value "100")
      (footprint "CAPC3216X19L")
      (description "Кер. ЧИП-конденсатор")
      (fields (field (name "MANUFACTURER") "WALSIN") (field (name "TOLERANCE") "±5%"))
      (libsource (lib "nels_caps") (part "Кер.ЧИП конд. 1206 100пФ NP0 5% 2000В"))
    )
    (comp (ref "C138")
      (value "47")
      (footprint "CAPC3216X19L")
      (description "Кер. ЧИП-конденсатор")
      (fields (field (name "MANUFACTURER") "WALSIN") (field (name "TOLERANCE") "±5%"))
      (libsource (lib "nels_caps") (part "Кер.ЧИП конд. 1206 47пФ NP0 5% 2000В"))
    )
    (comp (ref "C139")
      (value "47")
      (footprint "CAPC3216X19L")
      (description "Кер. ЧИП-конденсатор")
      (fields (field (name "MANUFACTURER") "WALSIN") (field (name "TOLERANCE") "±5%"))
      (libsource (lib "nels_caps") (part "Кер.ЧИП конд. 1206 47пФ NP0 5% 2000В"))
    )
    (comp (ref "C140")
      (value "100")
      (footprint "CAPC3216X19L")
      (description "Кер. ЧИП-конденсатор")
      (fields (field (name "MANUFACTURER") "WALSIN") (field (name "TOLERANCE") "±5%"))
      (libsource (lib "nels_caps") (part "Кер.ЧИП конд. 1206 100пФ NP0 5% 2000В"))
    )
    (comp (ref "C158")
      (value "0.01мк")
      (footprint "CAPC1005X06N")
      (description "Кер. ЧИП-конденсатор")
      (fields (field (name "TOLERANCE") "±20%"))
      (libsource (lib "nels_caps") (part "Кер.ЧИП конд. 0402 0.01мкФ X7R 10%, 50В"))
    )
    (comp (ref "C159")
      (value "0.01мк")
      (footprint "CAPC1005X06N")
      (description "Кер. ЧИП-конденсатор")
      (fields (field (name "TOLERANCE") "±20%"))
      (libsource (lib "nels_caps") (part "Кер.ЧИП конд. 0402 0.01мкФ X7R 10%, 50В"))
    )
    (comp (ref "C160")
      (value "0.01мк")
      (footprint "CAPC1005X06N")
      (description "Кер. ЧИП-конденсатор")
      (fields (field (name "TOLERANCE") "±20%"))
      (libsource (lib "nels_caps") (part "Кер.ЧИП конд. 0402 0.01мкФ X7R 10%, 50В"))
    )
    (comp (ref "C161")
      (value "0.01мк")
      (footprint "CAPC1005X06N")
      (description "Кер. ЧИП-конденсатор")
      (fields (field (name "TOLERANCE") "±20%"))
      (libsource (lib "nels_caps") (part "Кер.ЧИП конд. 0402 0.01мкФ X7R 10%, 50В"))
    )
    (comp (ref "C162")
      (value "0.01мк")
      (footprint "CAPC1005X06N")
      (description "Кер. ЧИП-конденсатор")
      (fields (field (name "TOLERANCE") "±20%"))
      (libsource (lib "nels_caps") (part "Кер.ЧИП конд. 0402 0.01мкФ X7R 10%, 50В"))
    )
    (comp (ref "C163")
      (value "0.01мк")
      (footprint "CAPC1005X06N")
      (description "Кер. ЧИП-конденсатор")
      (fields (field (name "TOLERANCE") "±20%"))
      (libsource (lib "nels_caps") (part "Кер.ЧИП конд. 0402 0.01мкФ X7R 10%, 50В"))
    )
    (comp (ref "C164")
      (value "0.01мк")
      (footprint "CAPC1005X06N")
      (description "Кер. ЧИП-конденсатор")
      (fields (field (name "TOLERANCE") "±20%"))
      (libsource (lib "nels_caps") (part "Кер.ЧИП конд. 0402 0.01мкФ X7R 10%, 50В"))
    )
    (comp (ref "K1")
      (value "HJR4102-L-12VDC-S-Z")
      (footprint "HJR4102")
      (description "Реле 1пер. 12VDC, 1A/240VAC")
      (libsource (lib "nels_other") (part "Реле HJR4102-L-12VDC-S-Z"))
    )
    (comp (ref "K2")
      (value "HJR4102-L-12VDC-S-Z")
      (footprint "HJR4102")
      (description "Реле 1пер. 12VDC, 1A/240VAC")
      (libsource (lib "nels_other") (part "Реле HJR4102-L-12VDC-S-Z"))
    )
    (comp (ref "K3")
      (value "HJR4102-L-12VDC-S-Z")
      (footprint "HJR4102")
      (description "Реле 1пер. 12VDC, 1A/240VAC")
      (libsource (lib "nels_other") (part "Реле HJR4102-L-12VDC-S-Z"))
    )
    (comp (ref "K4")
      (value "HJR4102-L-12VDC-S-Z")
      (footprint "HJR4102")
      (description "Реле 1пер. 12VDC, 1A/240VAC")
      (libsource (lib "nels_other") (part "Реле HJR4102-L-12VDC-S-Z"))
    )
    (comp (ref "K5")
      (value "HJR4102-L-12VDC-S-Z")
      (footprint "HJR4102")
      (description "Реле 1пер. 12VDC, 1A/240VAC")
      (libsource (lib "nels_other") (part "Реле HJR4102-L-12VDC-S-Z"))
    )
    (comp (ref "K6")
      (value "HJR4102-L-12VDC-S-Z")
      (footprint "HJR4102")
      (description "Реле 1пер. 12VDC, 1A/240VAC")
      (libsource (lib "nels_other") (part "Реле HJR4102-L-12VDC-S-Z"))
    )
    (comp (ref "K7")
      (value "HJR4102-L-12VDC-S-Z")
      (footprint "HJR4102")
      (description "Реле 1пер. 12VDC, 1A/240VAC")
      (libsource (lib "nels_other") (part "Реле HJR4102-L-12VDC-S-Z"))
    )
    (comp (ref "K8")
      (value "HJR4102-L-12VDC-S-Z")
      (footprint "HJR4102")
      (description "Реле 1пер. 12VDC, 1A/240VAC")
      (libsource (lib "nels_other") (part "Реле HJR4102-L-12VDC-S-Z"))
    )
    (comp (ref "K9")
      (value "HJR4102-L-12VDC-S-Z")
      (footprint "HJR4102")
      (description "Реле 1пер. 12VDC, 1A/240VAC")
      (libsource (lib "nels_other") (part "Реле HJR4102-L-12VDC-S-Z"))
    )
    (comp (ref "K10")
      (value "HJR4102-L-12VDC-S-Z")
      (footprint "HJR4102")
      (description "Реле 1пер. 12VDC, 1A/240VAC")
      (libsource (lib "nels_other") (part "Реле HJR4102-L-12VDC-S-Z"))
    )
    (comp (ref "K11")
      (value "HJR4102-L-12VDC-S-Z")
      (footprint "HJR4102")
      (description "Реле 1пер. 12VDC, 1A/240VAC")
      (libsource (lib "nels_other") (part "Реле HJR4102-L-12VDC-S-Z"))
    )
    (comp (ref "K12")
      (value "HJR4102-L-12VDC-S-Z")
      (footprint "HJR4102")
      (description "Реле 1пер. 12VDC, 1A/240VAC")
      (libsource (lib "nels_other") (part "Реле HJR4102-L-12VDC-S-Z"))
    )
    (comp (ref "K13")
      (value "HJR4102-L-12VDC-S-Z")
      (footprint "HJR4102")
      (description "Реле 1пер. 12VDC, 1A/240VAC")
      (libsource (lib "nels_other") (part "Реле HJR4102-L-12VDC-S-Z"))
    )
    (comp (ref "K14")
      (value "HJR4102-L-12VDC-S-Z")
      (footprint "HJR4102")
      (description "Реле 1пер. 12VDC, 1A/240VAC")
      (libsource (lib "nels_other") (part "Реле HJR4102-L-12VDC-S-Z"))
    )
    (comp (ref "L1")
      (value "2,2мкГн")
      (footprint "CSAB0420")
      (description "Molding Power Choke")
      (fields
        (field (name "MANUFACTURER") "Vishay")
        (field (name "MANUFACTURERPARTNUMBER") "IHLP1616ABER1R0M11")
      )
      (libsource (lib "nels_ind") (part "ЧИП индуктивность CSAB0420-2R2M"))
    )
    (comp (ref "L11")
      (value "4.79 мкГн")
      (footprint "T68-2")
      (description "29 витков")
      (libsource (lib "nels_ind") (part "Индуктивность T68-2 4.79 мкГн"))
    )
    (comp (ref "L12")
      (value "3.85 мкГн")
      (footprint "T68-2")
      (description "26 витков")
      (libsource (lib "nels_ind") (part "Индуктивность T68-2 3.85 мкГн"))
    )
    (comp (ref "L13")
      (value "3.85 мкГн")
      (footprint "T68-2")
      (description "26 витков")
      (libsource (lib "nels_ind") (part "Индуктивность T68-2 3.85 мкГн"))
    )
    (comp (ref "L14")
      (value "2.51 мкГн")
      (footprint "T68-2")
      (description "21 виток")
      (libsource (lib "nels_ind") (part "Индуктивность T68-2 2.51 мкГн"))
    )
    (comp (ref "L15")
      (value "2.28 мкГн")
      (footprint "T68-2")
      (libsource (lib "nels_ind") (part "Индуктивность T68-2 2.28 мкГн"))
    )
    (comp (ref "L16")
      (value "2.28 мкГн")
      (footprint "T68-2")
      (libsource (lib "nels_ind") (part "Индуктивность T68-2 2.28 мкГн"))
    )
    (comp (ref "L17")
      (value "1.48 мкГн")
      (footprint "T68-2")
      (description "16 витков")
      (libsource (lib "nels_ind") (part "Индуктивность T68-2 1.48 мкГн"))
    )
    (comp (ref "L18")
      (value "1.28 мкГн")
      (footprint "T68-2")
      (description "16 витков")
      (libsource (lib "nels_ind") (part "Индуктивность T68-2 1.28 мкГн"))
    )
    (comp (ref "L19")
      (value "1.28 мкГн")
      (footprint "T68-2")
      (description "16 витков")
      (libsource (lib "nels_ind") (part "Индуктивность T68-2 1.28 мкГн"))
    )
    (comp (ref "L20")
      (value "676 нГн")
      (footprint "T68-6")
      (description "12 витков")
      (libsource (lib "nels_ind") (part "Индуктивность T68-6 676 нГн"))
    )
    (comp (ref "L21")
      (value "470 нГн")
      (footprint "T68-6")
      (description "10 витков")
      (libsource (lib "nels_ind") (part "Индуктивность T68-6 470 нГн"))
    )
    (comp (ref "L22")
      (value "470 нГн")
      (footprint "T68-6")
      (description "10 витков")
      (libsource (lib "nels_ind") (part "Индуктивность T68-6 470 нГн"))
    )
    (comp (ref "L23")
      (value "177 нГн")
      (footprint "COIL D11 W4 L6")
      (description "4 витка, диаметр 11мм, длина 6мм")
      (libsource (lib "nels_ind") (part "Индуктивность 177 нГн"))
    )
    (comp (ref "L24")
      (value "470 нГн")
      (footprint "T68-6")
      (description "10 витков")
      (libsource (lib "nels_ind") (part "Индуктивность T68-6 470 нГн"))
    )
    (comp (ref "L25")
      (value "381 нГн")
      (footprint "T68-6")
      (description "9 витков")
      (libsource (lib "nels_ind") (part "Индуктивность T68-6 381 нГн"))
    )
    (comp (ref "L26")
      (value "130 нГн")
      (footprint "COIL D11 W4 L10")
      (description "4 витка, диаметр 11мм, длина 10мм")
      (libsource (lib "nels_ind") (part "Индуктивность 130 нГн"))
    )
    (comp (ref "L27")
      (value "470 нГн")
      (footprint "T68-6")
      (description "10 витков")
      (libsource (lib "nels_ind") (part "Индуктивность T68-6 470 нГн"))
    )
    (comp (ref "L28")
      (value "300 нГн")
      (footprint "T68-6")
      (description "8 витков")
      (libsource (lib "nels_ind") (part "Индуктивность T68-6 300 нГн"))
    )
    (comp (ref "L29")
      (value "130 нГн")
      (footprint "COIL D11 W4 L10")
      (description "4 витка, диаметр 11мм, длина 10мм")
      (libsource (lib "nels_ind") (part "Индуктивность 130 нГн"))
    )
    (comp (ref "L30")
      (value "381 нГн")
      (footprint "T68-6")
      (description "9 витков")
      (libsource (lib "nels_ind") (part "Индуктивность T68-6 381 нГн"))
    )
    (comp (ref "L31")
      (value "300 нГн")
      (footprint "T68-6")
      (description "8 витков")
      (libsource (lib "nels_ind") (part "Индуктивность T68-6 300 нГн"))
    )
    (comp (ref "XP1")
      (value "IDC2-14MS")
      (footprint "IDC2-14MS")
      (description "JTAG Xilinx IDC2-14MS")
      (fields (field (name "MANUFACTURER") "Molex"))
      (libsource (lib "nels_conn") (part "Соединитель IDC2-14MS"))
    )
    (comp (ref "XW1")
      (value "SMA-JR")
      (footprint "SMA-JR")
      (description "SMA-JR Разъем SMA гнездо на плату, прямой угол")
      (libsource (lib "") (part "Соединитель коаксиальный SMA-JR_1"))
    )
    (comp (ref "XW2")
      (value "SMA-JR")
      (footprint "SMA-JR")
      (description "SMA-JR Разъем SMA гнездо на плату, прямой угол")
      (libsource (lib "nels_conn") (part "Соединитель коаксиальный SMA-JR"))
    )
  )
  (nets
    (net (code "1") (name "GND") (class "Default")
      (node (ref "C1") (pin "1") (pinfunction "1_1") (pintype "passive"))
      (node (ref "C10") (pin "1") (pinfunction "1_1") (pintype "passive"))
      (node (ref "C100") (pin "2") (pinfunction "2_2") (pintype "passive"))
      (node (ref "C101") (pin "2") (pinfunction "2_2") (pintype "passive"))
      (node (ref "C103") (pin "2") (pinfunction "2_2") (pintype "passive"))
      (node (ref "C104") (pin "2") (pinfunction "2_2") (pintype "passive"))
      (node (ref "C105") (pin "2") (pinfunction "2_2") (pintype "passive"))
      (node (ref "C106") (pin "2") (pinfunction "2_2") (pintype "passive"))
      (node (ref "C107") (pin "2") (pinfunction "2_2") (pintype "passive"))
      (node (ref "C108") (pin "2") (pinfunction "2_2") (pintype "passive"))
      (node (ref "C109") (pin "2") (pinfunction "2_2") (pintype "passive"))
      (node (ref "C11") (pin "1") (pinfunction "1_1") (pintype "passive"))
      (node (ref "C110") (pin "2") (pinfunction "2_2") (pintype "passive"))
      (node (ref "C113") (pin "2") (pinfunction "2_2") (pintype "passive"))
      (node (ref "C115") (pin "2") (pinfunction "2_2") (pintype "passive"))
      (node (ref "C116") (pin "2") (pinfunction "2_2") (pintype "passive"))
      (node (ref "C117") (pin "2") (pinfunction "2_2") (pintype "passive"))
      (node (ref "C118") (pin "2") (pinfunction "2_2") (pintype "passive"))
      (node (ref "C12") (pin "1") (pinfunction "1_1") (pintype "passive"))
      (node (ref "C121") (pin "2") (pinfunction "2_2") (pintype "passive"))
      (node (ref "C122") (pin "2") (pinfunction "2_2") (pintype "passive"))
      (node (ref "C123") (pin "2") (pinfunction "2_2") (pintype "passive"))
      (node (ref "C128") (pin "2") (pinfunction "2_2") (pintype "passive"))
      (node (ref "C129") (pin "2") (pinfunction "2_2") (pintype "passive"))
      (node (ref "C13") (pin "1") (pinfunction "1_1") (pintype "passive"))
      (node (ref "C130") (pin "2") (pinfunction "2_2") (pintype "passive"))
      (node (ref "C132") (pin "2") (pinfunction "2_2") (pintype "passive"))
      (node (ref "C133") (pin "2") (pinfunction "2_2") (pintype "passive"))
      (node (ref "C134") (pin "2") (pinfunction "2_2") (pintype "passive"))
      (node (ref "C137") (pin "2") (pinfunction "2_2") (pintype "passive"))
      (node (ref "C138") (pin "2") (pinfunction "2_2") (pintype "passive"))
      (node (ref "C139") (pin "2") (pinfunction "2_2") (pintype "passive"))
      (node (ref "C14") (pin "1") (pinfunction "1_1") (pintype "passive"))
      (node (ref "C140") (pin "2") (pinfunction "2_2") (pintype "passive"))
      (node (ref "C15") (pin "1") (pinfunction "1_1") (pintype "passive"))
      (node (ref "C158") (pin "1") (pinfunction "1_1") (pintype "passive"))
      (node (ref "C159") (pin "1") (pinfunction "1_1") (pintype "passive"))
      (node (ref "C160") (pin "1") (pinfunction "1_1") (pintype "passive"))
      (node (ref "C161") (pin "1") (pinfunction "1_1") (pintype "passive"))
      (node (ref "C162") (pin "1") (pinfunction "1_1") (pintype "passive"))
      (node (ref "C163") (pin "1") (pinfunction "1_1") (pintype "passive"))
      (node (ref "C164") (pin "1") (pinfunction "1_1") (pintype "passive"))
      (node (ref "C2") (pin "1") (pinfunction "1_1") (pintype "passive"))
      (node (ref "C3") (pin "1") (pinfunction "1_1") (pintype "passive"))
      (node (ref "C4") (pin "1") (pinfunction "1_1") (pintype "passive"))
      (node (ref "C5") (pin "1") (pinfunction "1_1") (pintype "passive"))
      (node (ref "C50") (pin "2") (pinfunction "2_2") (pintype "passive"))
      (node (ref "C51") (pin "2") (pinfunction "2_2") (pintype "passive"))
      (node (ref "C52") (pin "2") (pinfunction "2_2") (pintype "passive"))
      (node (ref "C53") (pin "2") (pinfunction "2_2") (pintype "passive"))
      (node (ref "C56") (pin "2") (pinfunction "2_2") (pintype "passive"))
      (node (ref "C57") (pin "2") (pinfunction "2_2") (pintype "passive"))
      (node (ref "C59") (pin "2") (pinfunction "2_2") (pintype "passive"))
      (node (ref "C6") (pin "1") (pinfunction "1_1") (pintype "passive"))
      (node (ref "C60") (pin "2") (pinfunction "2_2") (pintype "passive"))
      (node (ref "C63") (pin "2") (pinfunction "2_2") (pintype "passive"))
      (node (ref "C64") (pin "2") (pinfunction "2_2") (pintype "passive"))
      (node (ref "C65") (pin "2") (pinfunction "2_2") (pintype "passive"))
      (node (ref "C66") (pin "2") (pinfunction "2_2") (pintype "passive"))
      (node (ref "C69") (pin "2") (pinfunction "2_2") (pintype "passive"))
      (node (ref "C7") (pin "1") (pinfunction "1_1") (pintype "passive"))
      (node (ref "C70") (pin "2") (pinfunction "2_2") (pintype "passive"))
      (node (ref "C73") (pin "2") (pinfunction "2_2") (pintype "passive"))
      (node (ref "C74") (pin "2") (pinfunction "2_2") (pintype "passive"))
      (node (ref "C77") (pin "2") (pinfunction "2_2") (pintype "passive"))
      (node (ref "C78") (pin "2") (pinfunction "2_2") (pintype "passive"))
      (node (ref "C8") (pin "1") (pinfunction "1_1") (pintype "passive"))
      (node (ref "C80") (pin "2") (pinfunction "2_2") (pintype "passive"))
      (node (ref "C81") (pin "2") (pinfunction "2_2") (pintype "passive"))
      (node (ref "C85") (pin "2") (pinfunction "2_2") (pintype "passive"))
      (node (ref "C86") (pin "2") (pinfunction "2_2") (pintype "passive"))
      (node (ref "C89") (pin "2") (pinfunction "2_2") (pintype "passive"))
      (node (ref "C9") (pin "1") (pinfunction "1_1") (pintype "passive"))
      (node (ref "C90") (pin "2") (pinfunction "2_2") (pintype "passive"))
      (node (ref "C92") (pin "2") (pinfunction "2_2") (pintype "passive"))
      (node (ref "C93") (pin "2") (pinfunction "2_2") (pintype "passive"))
      (node (ref "C94") (pin "2") (pinfunction "2_2") (pintype "passive"))
      (node (ref "C96") (pin "2") (pinfunction "2_2") (pintype "passive"))
      (node (ref "C97") (pin "2") (pinfunction "2_2") (pintype "passive"))
      (node (ref "K1") (pin "7") (pintype "passive"))
      (node (ref "K10") (pin "7") (pintype "passive"))
      (node (ref "K11") (pin "7") (pintype "passive"))
      (node (ref "K12") (pin "7") (pintype "passive"))
      (node (ref "K13") (pin "7") (pintype "passive"))
      (node (ref "K14") (pin "7") (pintype "passive"))
      (node (ref "K2") (pin "7") (pintype "passive"))
      (node (ref "K3") (pin "7") (pintype "passive"))
      (node (ref "K4") (pin "7") (pintype "passive"))
      (node (ref "K5") (pin "7") (pintype "passive"))
      (node (ref "K6") (pin "7") (pintype "passive"))
      (node (ref "K7") (pin "7") (pintype "passive"))
      (node (ref "K8") (pin "7") (pintype "passive"))
      (node (ref "K9") (pin "7") (pintype "passive"))
      (node (ref "XP1") (pin "11") (pinfunction "11_11") (pintype "passive"))
      (node (ref "XP1") (pin "13") (pinfunction "13_13") (pintype "passive"))
      (node (ref "XP1") (pin "5") (pinfunction "5_5") (pintype "passive"))
      (node (ref "XP1") (pin "7") (pinfunction "7_7") (pintype "passive"))
      (node (ref "XP1") (pin "9") (pinfunction "9_9") (pintype "passive"))
      (node (ref "XW1") (pin "2") (pinfunction "2_2") (pintype "passive"))
      (node (ref "XW2") (pin "2") (pinfunction "2_2") (pintype "passive"))
    )
    (net (code "2") (name "Net-(C50-Pad1)") (class "Default")
      (node (ref "C50") (pin "1") (pinfunction "1_1") (pintype "passive"))
      (node (ref "C79") (pin "2") (pinfunction "2_2") (pintype "passive"))
      (node (ref "C91") (pin "2") (pinfunction "2_2") (pintype "passive"))
      (node (ref "K5") (pin "12") (pintype "passive"))
      (node (ref "L17") (pin "1") (pinfunction "1_1") (pintype "passive"))
    )
    (net (code "3") (name "Net-(C51-Pad1)") (class "Default")
      (node (ref "C51") (pin "1") (pinfunction "1_1") (pintype "passive"))
      (node (ref "C52") (pin "1") (pinfunction "1_1") (pintype "passive"))
      (node (ref "C54") (pin "2") (pinfunction "2_2") (pintype "passive"))
      (node (ref "C55") (pin "2") (pinfunction "2_2") (pintype "passive"))
      (node (ref "K1") (pin "12") (pintype "passive"))
      (node (ref "L11") (pin "1") (pinfunction "1_1") (pintype "passive"))
    )
    (net (code "4") (name "Net-(C53-Pad1)") (class "Default")
      (node (ref "C53") (pin "1") (pinfunction "1_1") (pintype "passive"))
      (node (ref "C54") (pin "1") (pinfunction "1_1") (pintype "passive"))
      (node (ref "C55") (pin "1") (pinfunction "1_1") (pintype "passive"))
      (node (ref "C57") (pin "1") (pinfunction "1_1") (pintype "passive"))
      (node (ref "C58") (pin "2") (pinfunction "2_2") (pintype "passive"))
      (node (ref "C82") (pin "2") (pinfunction "2_2") (pintype "passive"))
      (node (ref "L11") (pin "2") (pinfunction "2_2") (pintype "passive"))
      (node (ref "L12") (pin "1") (pinfunction "1_1") (pintype "passive"))
    )
    (net (code "5") (name "Net-(C56-Pad1)") (class "Default")
      (node (ref "C56") (pin "1") (pinfunction "1_1") (pintype "passive"))
      (node (ref "C79") (pin "1") (pinfunction "1_1") (pintype "passive"))
      (node (ref "C80") (pin "1") (pinfunction "1_1") (pintype "passive"))
      (node (ref "C81") (pin "1") (pinfunction "1_1") (pintype "passive"))
      (node (ref "C83") (pin "2") (pinfunction "2_2") (pintype "passive"))
      (node (ref "C84") (pin "2") (pinfunction "2_2") (pintype "passive"))
      (node (ref "C91") (pin "1") (pinfunction "1_1") (pintype "passive"))
      (node (ref "L17") (pin "2") (pinfunction "2_2") (pintype "passive"))
      (node (ref "L18") (pin "1") (pinfunction "1_1") (pintype "passive"))
    )
    (net (code "6") (name "Net-(C58-Pad1)") (class "Default")
      (node (ref "C58") (pin "1") (pinfunction "1_1") (pintype "passive"))
      (node (ref "C59") (pin "1") (pinfunction "1_1") (pintype "passive"))
      (node (ref "C60") (pin "1") (pinfunction "1_1") (pintype "passive"))
      (node (ref "C61") (pin "2") (pinfunction "2_2") (pintype "passive"))
      (node (ref "C62") (pin "2") (pinfunction "2_2") (pintype "passive"))
      (node (ref "C82") (pin "1") (pinfunction "1_1") (pintype "passive"))
      (node (ref "L12") (pin "2") (pinfunction "2_2") (pintype "passive"))
      (node (ref "L13") (pin "1") (pinfunction "1_1") (pintype "passive"))
    )
    (net (code "7") (name "Net-(C61-Pad1)") (class "Default")
      (node (ref "C61") (pin "1") (pinfunction "1_1") (pintype "passive"))
      (node (ref "C62") (pin "1") (pinfunction "1_1") (pintype "passive"))
      (node (ref "C63") (pin "1") (pinfunction "1_1") (pintype "passive"))
      (node (ref "C64") (pin "1") (pinfunction "1_1") (pintype "passive"))
      (node (ref "K2") (pin "12") (pintype "passive"))
      (node (ref "L13") (pin "2") (pinfunction "2_2") (pintype "passive"))
    )
    (net (code "8") (name "Net-(C65-Pad1)") (class "Default")
      (node (ref "C65") (pin "1") (pinfunction "1_1") (pintype "passive"))
      (node (ref "C66") (pin "1") (pinfunction "1_1") (pintype "passive"))
      (node (ref "C67") (pin "2") (pinfunction "2_2") (pintype "passive"))
      (node (ref "C68") (pin "2") (pinfunction "2_2") (pintype "passive"))
      (node (ref "K3") (pin "12") (pintype "passive"))
      (node (ref "L14") (pin "1") (pinfunction "1_1") (pintype "passive"))
    )
    (net (code "9") (name "Net-(C67-Pad1)") (class "Default")
      (node (ref "C67") (pin "1") (pinfunction "1_1") (pintype "passive"))
      (node (ref "C68") (pin "1") (pinfunction "1_1") (pintype "passive"))
      (node (ref "C69") (pin "1") (pinfunction "1_1") (pintype "passive"))
      (node (ref "C70") (pin "1") (pinfunction "1_1") (pintype "passive"))
      (node (ref "C71") (pin "1") (pinfunction "1_1") (pintype "passive"))
      (node (ref "C72") (pin "2") (pinfunction "2_2") (pintype "passive"))
      (node (ref "L14") (pin "2") (pinfunction "2_2") (pintype "passive"))
      (node (ref "L15") (pin "1") (pinfunction "1_1") (pintype "passive"))
    )
    (net (code "10") (name "Net-(C71-Pad2)") (class "Default")
      (node (ref "C71") (pin "2") (pinfunction "2_2") (pintype "passive"))
      (node (ref "C72") (pin "1") (pinfunction "1_1") (pintype "passive"))
      (node (ref "C73") (pin "1") (pinfunction "1_1") (pintype "passive"))
      (node (ref "C74") (pin "1") (pinfunction "1_1") (pintype "passive"))
      (node (ref "C75") (pin "2") (pinfunction "2_2") (pintype "passive"))
      (node (ref "C76") (pin "2") (pinfunction "2_2") (pintype "passive"))
      (node (ref "L15") (pin "2") (pinfunction "2_2") (pintype "passive"))
      (node (ref "L16") (pin "1") (pinfunction "1_1") (pintype "passive"))
    )
    (net (code "11") (name "Net-(C75-Pad1)") (class "Default")
      (node (ref "C75") (pin "1") (pinfunction "1_1") (pintype "passive"))
      (node (ref "C76") (pin "1") (pinfunction "1_1") (pintype "passive"))
      (node (ref "C77") (pin "1") (pinfunction "1_1") (pintype "passive"))
      (node (ref "C78") (pin "1") (pinfunction "1_1") (pintype "passive"))
      (node (ref "K4") (pin "12") (pintype "passive"))
      (node (ref "L16") (pin "2") (pinfunction "2_2") (pintype "passive"))
    )
    (net (code "12") (name "Net-(C83-Pad1)") (class "Default")
      (node (ref "C83") (pin "1") (pinfunction "1_1") (pintype "passive"))
      (node (ref "C84") (pin "1") (pinfunction "1_1") (pintype "passive"))
      (node (ref "C85") (pin "1") (pinfunction "1_1") (pintype "passive"))
      (node (ref "C86") (pin "1") (pinfunction "1_1") (pintype "passive"))
      (node (ref "C87") (pin "2") (pinfunction "2_2") (pintype "passive"))
      (node (ref "C88") (pin "2") (pinfunction "2_2") (pintype "passive"))
      (node (ref "C89") (pin "1") (pinfunction "1_1") (pintype "passive"))
      (node (ref "L18") (pin "2") (pinfunction "2_2") (pintype "passive"))
      (node (ref "L19") (pin "1") (pinfunction "1_1") (pintype "passive"))
    )
    (net (code "13") (name "Net-(C87-Pad1)") (class "Default")
      (node (ref "C87") (pin "1") (pinfunction "1_1") (pintype "passive"))
      (node (ref "C88") (pin "1") (pinfunction "1_1") (pintype "passive"))
      (node (ref "C90") (pin "1") (pinfunction "1_1") (pintype "passive"))
      (node (ref "C92") (pin "1") (pinfunction "1_1") (pintype "passive"))
      (node (ref "K6") (pin "12") (pintype "passive"))
      (node (ref "L19") (pin "2") (pinfunction "2_2") (pintype "passive"))
    )
    (net (code "14") (name "Net-(C93-Pad1)") (class "Default")
      (node (ref "C93") (pin "1") (pinfunction "1_1") (pintype "passive"))
      (node (ref "C94") (pin "1") (pinfunction "1_1") (pintype "passive"))
      (node (ref "C95") (pin "2") (pinfunction "2_2") (pintype "passive"))
      (node (ref "K7") (pin "12") (pintype "passive"))
      (node (ref "L20") (pin "1") (pinfunction "1_1") (pintype "passive"))
    )
    (net (code "15") (name "Net-(C100-Pad1)") (class "Default")
      (node (ref "C100") (pin "1") (pinfunction "1_1") (pintype "passive"))
      (node (ref "C95") (pin "1") (pinfunction "1_1") (pintype "passive"))
      (node (ref "C96") (pin "1") (pinfunction "1_1") (pintype "passive"))
      (node (ref "C97") (pin "1") (pinfunction "1_1") (pintype "passive"))
      (node (ref "C98") (pin "2") (pinfunction "2_2") (pintype "passive"))
      (node (ref "C99") (pin "2") (pinfunction "2_2") (pintype "passive"))
      (node (ref "L20") (pin "2") (pinfunction "2_2") (pintype "passive"))
      (node (ref "L21") (pin "1") (pinfunction "1_1") (pintype "passive"))
    )
    (net (code "16") (name "Net-(C101-Pad1)") (class "Default")
      (node (ref "C101") (pin "1") (pinfunction "1_1") (pintype "passive"))
      (node (ref "C102") (pin "2") (pinfunction "2_2") (pintype "passive"))
      (node (ref "C103") (pin "1") (pinfunction "1_1") (pintype "passive"))
      (node (ref "C98") (pin "1") (pinfunction "1_1") (pintype "passive"))
      (node (ref "C99") (pin "1") (pinfunction "1_1") (pintype "passive"))
      (node (ref "L21") (pin "2") (pinfunction "2_2") (pintype "passive"))
      (node (ref "L22") (pin "1") (pinfunction "1_1") (pintype "passive"))
    )
    (net (code "17") (name "Net-(C102-Pad1)") (class "Default")
      (node (ref "C102") (pin "1") (pinfunction "1_1") (pintype "passive"))
      (node (ref "C104") (pin "1") (pinfunction "1_1") (pintype "passive"))
      (node (ref "C105") (pin "1") (pinfunction "1_1") (pintype "passive"))
      (node (ref "K8") (pin "12") (pintype "passive"))
      (node (ref "L22") (pin "2") (pinfunction "2_2") (pintype "passive"))
    )
    (net (code "18") (name "Net-(C106-Pad1)") (class "Default")
      (node (ref "C106") (pin "1") (pinfunction "1_1") (pintype "passive"))
      (node (ref "C110") (pin "1") (pinfunction "1_1") (pintype "passive"))
      (node (ref "C111") (pin "2") (pinfunction "2_2") (pintype "passive"))
      (node (ref "K11") (pin "12") (pintype "passive"))
      (node (ref "L23") (pin "1") (pinfunction "1_1") (pintype "passive"))
    )
    (net (code "19") (name "Net-(C107-Pad1)") (class "Default")
      (node (ref "C107") (pin "1") (pinfunction "1_1") (pintype "passive"))
      (node (ref "C109") (pin "1") (pinfunction "1_1") (pintype "passive"))
      (node (ref "C114") (pin "2") (pinfunction "2_2") (pintype "passive"))
      (node (ref "K10") (pin "12") (pintype "passive"))
      (node (ref "L25") (pin "1") (pinfunction "1_1") (pintype "passive"))
    )
    (net (code "20") (name "Net-(C108-Pad1)") (class "Default")
      (node (ref "C108") (pin "1") (pinfunction "1_1") (pintype "passive"))
      (node (ref "C112") (pin "2") (pinfunction "2_2") (pintype "passive"))
      (node (ref "C113") (pin "1") (pinfunction "1_1") (pintype "passive"))
      (node (ref "K9") (pin "12") (pintype "passive"))
      (node (ref "L24") (pin "1") (pinfunction "1_1") (pintype "passive"))
    )
    (net (code "21") (name "Net-(C111-Pad1)") (class "Default")
      (node (ref "C111") (pin "1") (pinfunction "1_1") (pintype "passive"))
      (node (ref "C116") (pin "1") (pinfunction "1_1") (pintype "passive"))
      (node (ref "C119") (pin "2") (pinfunction "2_2") (pintype "passive"))
      (node (ref "C120") (pin "2") (pinfunction "2_2") (pintype "passive"))
      (node (ref "L23") (pin "2") (pinfunction "2_2") (pintype "passive"))
      (node (ref "L26") (pin "1") (pinfunction "1_1") (pintype "passive"))
    )
    (net (code "22") (name "Net-(C112-Pad1)") (class "Default")
      (node (ref "C112") (pin "1") (pinfunction "1_1") (pintype "passive"))
      (node (ref "C117") (pin "1") (pinfunction "1_1") (pintype "passive"))
      (node (ref "C122") (pin "1") (pinfunction "1_1") (pintype "passive"))
      (node (ref "C124") (pin "2") (pinfunction "2_2") (pintype "passive"))
      (node (ref "C125") (pin "2") (pinfunction "2_2") (pintype "passive"))
      (node (ref "L24") (pin "2") (pinfunction "2_2") (pintype "passive"))
      (node (ref "L27") (pin "1") (pinfunction "1_1") (pintype "passive"))
    )
    (net (code "23") (name "Net-(C114-Pad1)") (class "Default")
      (node (ref "C114") (pin "1") (pinfunction "1_1") (pintype "passive"))
      (node (ref "C115") (pin "1") (pinfunction "1_1") (pintype "passive"))
      (node (ref "C118") (pin "1") (pinfunction "1_1") (pintype "passive"))
      (node (ref "C123") (pin "1") (pinfunction "1_1") (pintype "passive"))
      (node (ref "C126") (pin "2") (pinfunction "2_2") (pintype "passive"))
      (node (ref "C127") (pin "2") (pinfunction "2_2") (pintype "passive"))
      (node (ref "L25") (pin "2") (pinfunction "2_2") (pintype "passive"))
      (node (ref "L28") (pin "1") (pinfunction "1_1") (pintype "passive"))
    )
    (net (code "24") (name "Net-(C119-Pad1)") (class "Default")
      (node (ref "C119") (pin "1") (pinfunction "1_1") (pintype "passive"))
      (node (ref "C120") (pin "1") (pinfunction "1_1") (pintype "passive"))
      (node (ref "C121") (pin "1") (pinfunction "1_1") (pintype "passive"))
      (node (ref "C128") (pin "1") (pinfunction "1_1") (pintype "passive"))
      (node (ref "C131") (pin "2") (pinfunction "2_2") (pintype "passive"))
      (node (ref "L26") (pin "2") (pinfunction "2_2") (pintype "passive"))
      (node (ref "L29") (pin "1") (pinfunction "1_1") (pintype "passive"))
    )
    (net (code "25") (name "Net-(C124-Pad1)") (class "Default")
      (node (ref "C124") (pin "1") (pinfunction "1_1") (pintype "passive"))
      (node (ref "C125") (pin "1") (pinfunction "1_1") (pintype "passive"))
      (node (ref "C129") (pin "1") (pinfunction "1_1") (pintype "passive"))
      (node (ref "C132") (pin "1") (pinfunction "1_1") (pintype "passive"))
      (node (ref "C135") (pin "2") (pinfunction "2_2") (pintype "passive"))
      (node (ref "L27") (pin "2") (pinfunction "2_2") (pintype "passive"))
      (node (ref "L30") (pin "1") (pinfunction "1_1") (pintype "passive"))
    )
    (net (code "26") (name "Net-(C126-Pad1)") (class "Default")
      (node (ref "C126") (pin "1") (pinfunction "1_1") (pintype "passive"))
      (node (ref "C127") (pin "1") (pinfunction "1_1") (pintype "passive"))
      (node (ref "C130") (pin "1") (pinfunction "1_1") (pintype "passive"))
      (node (ref "C133") (pin "1") (pinfunction "1_1") (pintype "passive"))
      (node (ref "C136") (pin "2") (pinfunction "2_2") (pintype "passive"))
      (node (ref "C138") (pin "1") (pinfunction "1_1") (pintype "passive"))
      (node (ref "L28") (pin "2") (pinfunction "2_2") (pintype "passive"))
      (node (ref "L31") (pin "1") (pinfunction "1_1") (pintype "passive"))
    )
    (net (code "27") (name "Net-(C131-Pad1)") (class "Default")
      (node (ref "C131") (pin "1") (pinfunction "1_1") (pintype "passive"))
      (node (ref "C134") (pin "1") (pinfunction "1_1") (pintype "passive"))
      (node (ref "K14") (pin "12") (pintype "passive"))
      (node (ref "L29") (pin "2") (pinfunction "2_2") (pintype "passive"))
    )
    (net (code "28") (name "Net-(C135-Pad1)") (class "Default")
      (node (ref "C135") (pin "1") (pinfunction "1_1") (pintype "passive"))
      (node (ref "C137") (pin "1") (pinfunction "1_1") (pintype "passive"))
      (node (ref "C139") (pin "1") (pinfunction "1_1") (pintype "passive"))
      (node (ref "K12") (pin "12") (pintype "passive"))
      (node (ref "L30") (pin "2") (pinfunction "2_2") (pintype "passive"))
    )
    (net (code "29") (name "Net-(C136-Pad1)") (class "Default")
      (node (ref "C136") (pin "1") (pinfunction "1_1") (pintype "passive"))
      (node (ref "C140") (pin "1") (pinfunction "1_1") (pintype "passive"))
      (node (ref "K13") (pin "12") (pintype "passive"))
      (node (ref "L31") (pin "2") (pinfunction "2_2") (pintype "passive"))
    )
    (net (code "30") (name "Net-(K1-Pad6)") (class "Default")
      (node (ref "K1") (pin "6") (pintype "passive"))
      (node (ref "K10") (pin "6") (pintype "passive"))
      (node (ref "K11") (pin "6") (pintype "passive"))
      (node (ref "K3") (pin "6") (pintype "passive"))
      (node (ref "K5") (pin "6") (pintype "passive"))
      (node (ref "K7") (pin "6") (pintype "passive"))
      (node (ref "K9") (pin "6") (pintype "passive"))
      (node (ref "XW1") (pin "1") (pinfunction "1_1") (pintype "passive"))
    )
    (net (code "31") (name "Net-(K12-Pad6)") (class "Default")
      (node (ref "K12") (pin "6") (pintype "passive"))
      (node (ref "K13") (pin "6") (pintype "passive"))
      (node (ref "K14") (pin "6") (pintype "passive"))
      (node (ref "K2") (pin "6") (pintype "passive"))
      (node (ref "K4") (pin "6") (pintype "passive"))
      (node (ref "K6") (pin "6") (pintype "passive"))
      (node (ref "K8") (pin "6") (pintype "passive"))
      (node (ref "XW2") (pin "1") (pinfunction "1_1") (pintype "passive"))
    )
    (net (code "32") (name "Net-(L1-Pad1)") (class "Default")
      (node (ref "L1") (pin "1") (pinfunction "1_1") (pintype "passive"))
      (node (ref "XP1") (pin "1") (pinfunction "1_1") (pintype "passive"))
      (node (ref "XP1") (pin "3") (pinfunction "3_3") (pintype "passive"))
    )
    (net (code "33") (name "RELAY0") (class "Default")
      (node (ref "C9") (pin "2") (pinfunction "2_2") (pintype "passive"))
      (node (ref "K11") (pin "5") (pintype "passive"))
      (node (ref "K14") (pin "5") (pintype "passive"))
      (node (ref "XP1") (pin "2") (pinfunction "2_2") (pintype "passive"))
    )
    (net (code "34") (name "RELAY1") (class "Default")
      (node (ref "C10") (pin "2") (pinfunction "2_2") (pintype "passive"))
      (node (ref "K10") (pin "5") (pintype "passive"))
      (node (ref "K13") (pin "5") (pintype "passive"))
      (node (ref "XP1") (pin "4") (pinfunction "4_4") (pintype "passive"))
    )
    (net (code "35") (name "RELAY2") (class "Default")
      (node (ref "C11") (pin "2") (pinfunction "2_2") (pintype "passive"))
      (node (ref "K12") (pin "5") (pintype "passive"))
      (node (ref "K9") (pin "5") (pintype "passive"))
      (node (ref "XP1") (pin "6") (pinfunction "6_6") (pintype "passive"))
    )
    (net (code "36") (name "RELAY3") (class "Default")
      (node (ref "C12") (pin "2") (pinfunction "2_2") (pintype "passive"))
      (node (ref "K7") (pin "5") (pintype "passive"))
      (node (ref "K8") (pin "5") (pintype "passive"))
      (node (ref "XP1") (pin "8") (pinfunction "8_8") (pintype "passive"))
    )
    (net (code "37") (name "RELAY4") (class "Default")
      (node (ref "C13") (pin "2") (pinfunction "2_2") (pintype "passive"))
      (node (ref "K5") (pin "5") (pintype "passive"))
      (node (ref "K6") (pin "5") (pintype "passive"))
      (node (ref "XP1") (pin "10") (pinfunction "10_10") (pintype "passive"))
    )
    (net (code "38") (name "RELAY5") (class "Default")
      (node (ref "C14") (pin "2") (pinfunction "2_2") (pintype "passive"))
      (node (ref "K3") (pin "5") (pintype "passive"))
      (node (ref "K4") (pin "5") (pintype "passive"))
      (node (ref "XP1") (pin "12") (pinfunction "12_12") (pintype "passive"))
    )
    (net (code "39") (name "RELAY6") (class "Default")
      (node (ref "C15") (pin "2") (pinfunction "2_2") (pintype "passive"))
      (node (ref "K1") (pin "5") (pintype "passive"))
      (node (ref "K2") (pin "5") (pintype "passive"))
      (node (ref "XP1") (pin "14") (pinfunction "14_14") (pintype "passive"))
    )
    (net (code "40") (name "VDD_12V") (class "Default")
      (node (ref "C1") (pin "2") (pinfunction "2_2") (pintype "passive"))
      (node (ref "C158") (pin "2") (pinfunction "2_2") (pintype "passive"))
      (node (ref "C159") (pin "2") (pinfunction "2_2") (pintype "passive"))
      (node (ref "C160") (pin "2") (pinfunction "2_2") (pintype "passive"))
      (node (ref "C161") (pin "2") (pinfunction "2_2") (pintype "passive"))
      (node (ref "C162") (pin "2") (pinfunction "2_2") (pintype "passive"))
      (node (ref "C163") (pin "2") (pinfunction "2_2") (pintype "passive"))
      (node (ref "C164") (pin "2") (pinfunction "2_2") (pintype "passive"))
      (node (ref "C2") (pin "2") (pinfunction "2_2") (pintype "passive"))
      (node (ref "C3") (pin "2") (pinfunction "2_2") (pintype "passive"))
      (node (ref "C4") (pin "2") (pinfunction "2_2") (pintype "passive"))
      (node (ref "C5") (pin "2") (pinfunction "2_2") (pintype "passive"))
      (node (ref "C6") (pin "2") (pinfunction "2_2") (pintype "passive"))
      (node (ref "C7") (pin "2") (pinfunction "2_2") (pintype "passive"))
      (node (ref "C8") (pin "2") (pinfunction "2_2") (pintype "passive"))
      (node (ref "K1") (pin "8") (pintype "passive"))
      (node (ref "K10") (pin "8") (pintype "passive"))
      (node (ref "K11") (pin "8") (pintype "passive"))
      (node (ref "K12") (pin "8") (pintype "passive"))
      (node (ref "K13") (pin "8") (pintype "passive"))
      (node (ref "K14") (pin "8") (pintype "passive"))
      (node (ref "K2") (pin "8") (pintype "passive"))
      (node (ref "K3") (pin "8") (pintype "passive"))
      (node (ref "K4") (pin "8") (pintype "passive"))
      (node (ref "K5") (pin "8") (pintype "passive"))
      (node (ref "K6") (pin "8") (pintype "passive"))
      (node (ref "K7") (pin "8") (pintype "passive"))
      (node (ref "K8") (pin "8") (pintype "passive"))
      (node (ref "K9") (pin "8") (pintype "passive"))
      (node (ref "L1") (pin "2") (pinfunction "2_2") (pintype "passive"))
    )
  )
)
